# logoi.net
KiCad netlist of a schematic drawn in EAGLE
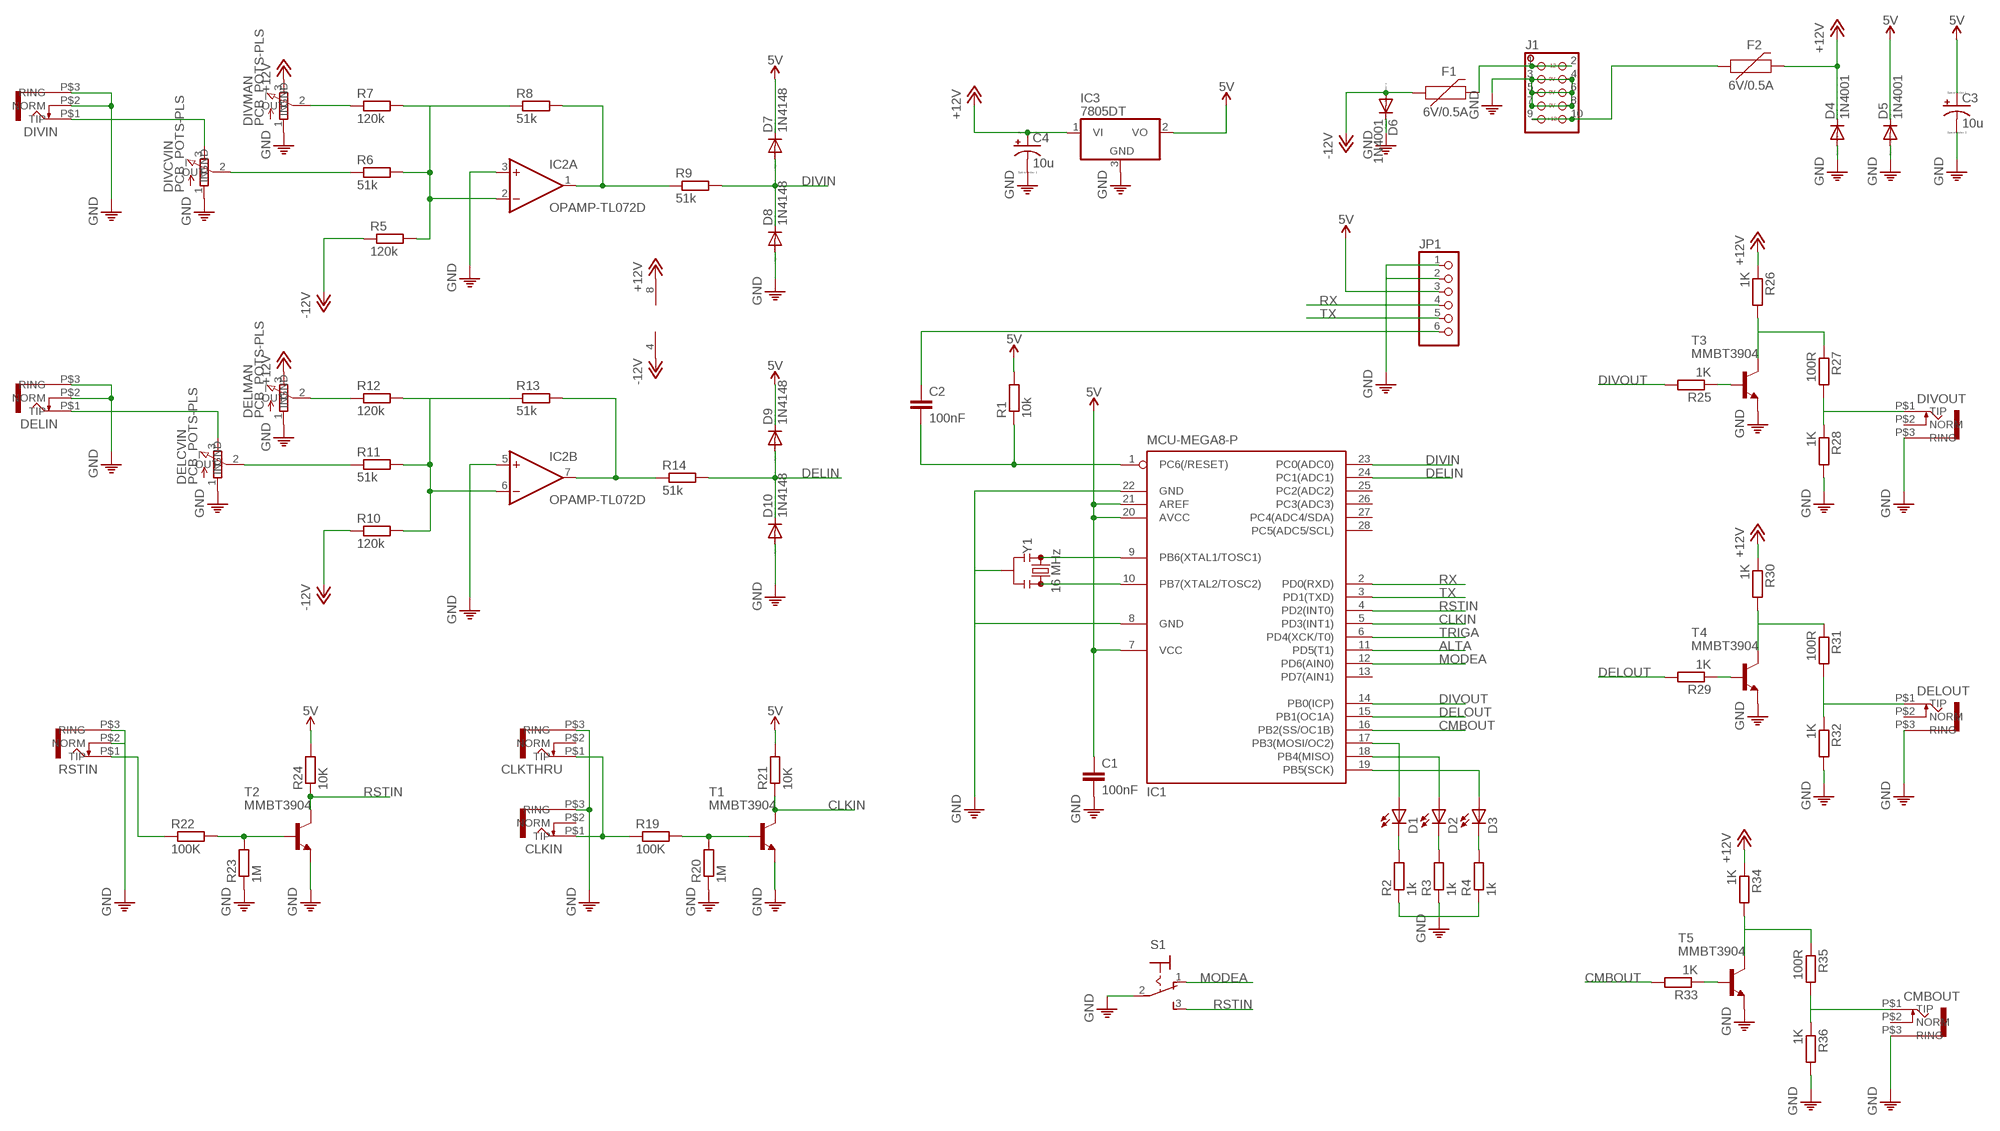
[diagram p0: schematic, sheet 1]

(export (version "E")
  (design (tool "Eeschema 10.0.6"))
  (components
    (comp (ref "C1")
      (value "100nF")
      (footprint "eagle-import:C0603")
      (libsource (lib "eagle-import") (part "CAPACITOR-EUC0603"))
    )
    (comp (ref "C2")
      (value "100nF")
      (footprint "eagle-import:C0603")
      (libsource (lib "eagle-import") (part "CAPACITOR-EUC0603"))
    )
    (comp (ref "C3")
      (value "10u")
      (footprint "eagle-import:E2,5-5")
      (libsource (lib "eagle-import") (part "CAPACITOR_POLARIZED-USE2.5-5"))
    )
    (comp (ref "C4")
      (value "10u")
      (footprint "eagle-import:E2,5-5")
      (libsource (lib "eagle-import") (part "CAPACITOR_POLARIZED-USE2.5-5"))
    )
    (comp (ref "CLKIN")
      (value "VERTICALJACKS")
      (footprint "eagle-import:KOBICONN_PJM301DM_JACK")
      (libsource (lib "eagle-import") (part "VERTICALJACKS"))
    )
    (comp (ref "CLKTHRU")
      (value "VERTICALJACKS")
      (footprint "eagle-import:KOBICONN_PJM301DM_JACK")
      (libsource (lib "eagle-import") (part "VERTICALJACKS"))
    )
    (comp (ref "CMBOUT")
      (value "VERTICALJACKS")
      (footprint "eagle-import:KOBICONN_PJM301DM_JACK")
      (libsource (lib "eagle-import") (part "VERTICALJACKS"))
    )
    (comp (ref "D1")
      (value "LED3MM")
      (footprint "eagle-import:LED3MM")
      (libsource (lib "eagle-import") (part "LED3MM"))
    )
    (comp (ref "D2")
      (value "LED3MM")
      (footprint "eagle-import:LED3MM")
      (libsource (lib "eagle-import") (part "LED3MM"))
    )
    (comp (ref "D3")
      (value "LED3MM")
      (footprint "eagle-import:LED3MM")
      (libsource (lib "eagle-import") (part "LED3MM"))
    )
    (comp (ref "D4")
      (value "1N4001")
      (footprint "eagle-import:DO-214AC")
      (libsource (lib "eagle-import") (part "DIODE-DO-214AC"))
    )
    (comp (ref "D5")
      (value "1N4001")
      (footprint "eagle-import:DO-214AC")
      (libsource (lib "eagle-import") (part "DIODE-DO-214AC"))
    )
    (comp (ref "D6")
      (value "1N4001")
      (footprint "eagle-import:DO-214AC")
      (libsource (lib "eagle-import") (part "DIODE-DO-214AC"))
    )
    (comp (ref "D7")
      (value "1N4148")
      (footprint "eagle-import:SOD323W_INFINEON")
      (libsource (lib "eagle-import") (part "DIODE-1N4148SOD-323"))
    )
    (comp (ref "D8")
      (value "1N4148")
      (footprint "eagle-import:SOD323W_INFINEON")
      (libsource (lib "eagle-import") (part "DIODE-1N4148SOD-323"))
    )
    (comp (ref "D9")
      (value "1N4148")
      (footprint "eagle-import:SOD323W_INFINEON")
      (libsource (lib "eagle-import") (part "DIODE-1N4148SOD-323"))
    )
    (comp (ref "D10")
      (value "1N4148")
      (footprint "eagle-import:SOD323W_INFINEON")
      (libsource (lib "eagle-import") (part "DIODE-1N4148SOD-323"))
    )
    (comp (ref "DELCVIN")
      (value "PCB_POTS-PLS")
      (footprint "eagle-import:9MM_PLS")
      (libsource (lib "eagle-import") (part "PCB_POTS-PLS"))
    )
    (comp (ref "DELIN")
      (value "VERTICALJACKS")
      (footprint "eagle-import:KOBICONN_PJM301DM_JACK")
      (libsource (lib "eagle-import") (part "VERTICALJACKS"))
    )
    (comp (ref "DELMAN")
      (value "PCB_POTS-PLS")
      (footprint "eagle-import:9MM_PLS")
      (libsource (lib "eagle-import") (part "PCB_POTS-PLS"))
    )
    (comp (ref "DELOUT")
      (value "VERTICALJACKS")
      (footprint "eagle-import:KOBICONN_PJM301DM_JACK")
      (libsource (lib "eagle-import") (part "VERTICALJACKS"))
    )
    (comp (ref "DIVCVIN")
      (value "PCB_POTS-PLS")
      (footprint "eagle-import:9MM_PLS")
      (libsource (lib "eagle-import") (part "PCB_POTS-PLS"))
    )
    (comp (ref "DIVIN")
      (value "VERTICALJACKS")
      (footprint "eagle-import:KOBICONN_PJM301DM_JACK")
      (libsource (lib "eagle-import") (part "VERTICALJACKS"))
    )
    (comp (ref "DIVMAN")
      (value "PCB_POTS-PLS")
      (footprint "eagle-import:9MM_PLS")
      (libsource (lib "eagle-import") (part "PCB_POTS-PLS"))
    )
    (comp (ref "DIVOUT")
      (value "VERTICALJACKS")
      (footprint "eagle-import:KOBICONN_PJM301DM_JACK")
      (libsource (lib "eagle-import") (part "VERTICALJACKS"))
    )
    (comp (ref "F1")
      (value "6V/0.5A")
      (footprint "eagle-import:1206")
      (libsource (lib "eagle-import") (part "FUSE-PPTC_HALF-AMP"))
    )
    (comp (ref "F2")
      (value "6V/0.5A")
      (footprint "eagle-import:1206")
      (libsource (lib "eagle-import") (part "FUSE-PPTC_HALF-AMP"))
    )
    (comp (ref "IC1")
      (value "MCU-MEGA8-P")
      (footprint "eagle-import:DIL28-3")
      (libsource (lib "eagle-import") (part "MCU-MEGA8-P"))
    )
    (comp (ref "IC2")
      (value "OPAMP-TL072D")
      (footprint "eagle-import:SO08")
      (libsource (lib "eagle-import") (part "OPAMP-TL072D"))
    )
    (comp (ref "IC3")
      (value "7805DT")
      (footprint "eagle-import:TO252")
      (libsource (lib "eagle-import") (part "78DT05"))
    )
    (comp (ref "J1")
      (value "HEADER-EUROPWR_2X05-OPEN")
      (footprint "eagle-import:2X05_EUROPWR_OPEN")
      (libsource (lib "eagle-import") (part "HEADER-EUROPWR_2X05-OPEN"))
    )
    (comp (ref "JP1")
      (value "PINHD-1X6")
      (footprint "eagle-import:1X06")
      (libsource (lib "eagle-import") (part "PINHD-1X6"))
    )
    (comp (ref "R1")
      (value "10k")
      (footprint "eagle-import:R0603")
      (libsource (lib "eagle-import") (part "RESISTOR-EU_R0603"))
    )
    (comp (ref "R2")
      (value "1k")
      (footprint "eagle-import:R0603")
      (libsource (lib "eagle-import") (part "RESISTOR-EU_R0603"))
    )
    (comp (ref "R3")
      (value "1k")
      (footprint "eagle-import:R0603")
      (libsource (lib "eagle-import") (part "RESISTOR-EU_R0603"))
    )
    (comp (ref "R4")
      (value "1k")
      (footprint "eagle-import:R0603")
      (libsource (lib "eagle-import") (part "RESISTOR-EU_R0603"))
    )
    (comp (ref "R5")
      (value "120k")
      (footprint "eagle-import:R0603")
      (libsource (lib "eagle-import") (part "RESISTOR-EU_R0603"))
    )
    (comp (ref "R6")
      (value "51k")
      (footprint "eagle-import:R0603")
      (libsource (lib "eagle-import") (part "RESISTOR-EU_R0603"))
    )
    (comp (ref "R7")
      (value "120k")
      (footprint "eagle-import:R0603")
      (libsource (lib "eagle-import") (part "RESISTOR-EU_R0603"))
    )
    (comp (ref "R8")
      (value "51k")
      (footprint "eagle-import:R0603")
      (libsource (lib "eagle-import") (part "RESISTOR-EU_R0603"))
    )
    (comp (ref "R9")
      (value "51k")
      (footprint "eagle-import:R0603")
      (libsource (lib "eagle-import") (part "RESISTOR-EU_R0603"))
    )
    (comp (ref "R10")
      (value "120k")
      (footprint "eagle-import:R0603")
      (libsource (lib "eagle-import") (part "RESISTOR-EU_R0603"))
    )
    (comp (ref "R11")
      (value "51k")
      (footprint "eagle-import:R0603")
      (libsource (lib "eagle-import") (part "RESISTOR-EU_R0603"))
    )
    (comp (ref "R12")
      (value "120k")
      (footprint "eagle-import:R0603")
      (libsource (lib "eagle-import") (part "RESISTOR-EU_R0603"))
    )
    (comp (ref "R13")
      (value "51k")
      (footprint "eagle-import:R0603")
      (libsource (lib "eagle-import") (part "RESISTOR-EU_R0603"))
    )
    (comp (ref "R14")
      (value "51k")
      (footprint "eagle-import:R0603")
      (libsource (lib "eagle-import") (part "RESISTOR-EU_R0603"))
    )
    (comp (ref "R19")
      (value "100K")
      (footprint "eagle-import:R0603")
      (libsource (lib "eagle-import") (part "RESISTOR-EU_R0603"))
    )
    (comp (ref "R20")
      (value "1M")
      (footprint "eagle-import:R0603")
      (libsource (lib "eagle-import") (part "RESISTOR-EU_R0603"))
    )
    (comp (ref "R21")
      (value "10K")
      (footprint "eagle-import:R0603")
      (libsource (lib "eagle-import") (part "RESISTOR-EU_R0603"))
    )
    (comp (ref "R22")
      (value "100K")
      (footprint "eagle-import:R0603")
      (libsource (lib "eagle-import") (part "RESISTOR-EU_R0603"))
    )
    (comp (ref "R23")
      (value "1M")
      (footprint "eagle-import:R0603")
      (libsource (lib "eagle-import") (part "RESISTOR-EU_R0603"))
    )
    (comp (ref "R24")
      (value "10K")
      (footprint "eagle-import:R0603")
      (libsource (lib "eagle-import") (part "RESISTOR-EU_R0603"))
    )
    (comp (ref "R25")
      (value "1K")
      (footprint "eagle-import:R0603")
      (libsource (lib "eagle-import") (part "RESISTOR-EU_R0603"))
    )
    (comp (ref "R26")
      (value "1K")
      (footprint "eagle-import:R0603")
      (libsource (lib "eagle-import") (part "RESISTOR-EU_R0603"))
    )
    (comp (ref "R27")
      (value "100R")
      (footprint "eagle-import:R0603")
      (libsource (lib "eagle-import") (part "RESISTOR-EU_R0603"))
    )
    (comp (ref "R28")
      (value "1K")
      (footprint "eagle-import:R0603")
      (libsource (lib "eagle-import") (part "RESISTOR-EU_R0603"))
    )
    (comp (ref "R29")
      (value "1K")
      (footprint "eagle-import:R0603")
      (libsource (lib "eagle-import") (part "RESISTOR-EU_R0603"))
    )
    (comp (ref "R30")
      (value "1K")
      (footprint "eagle-import:R0603")
      (libsource (lib "eagle-import") (part "RESISTOR-EU_R0603"))
    )
    (comp (ref "R31")
      (value "100R")
      (footprint "eagle-import:R0603")
      (libsource (lib "eagle-import") (part "RESISTOR-EU_R0603"))
    )
    (comp (ref "R32")
      (value "1K")
      (footprint "eagle-import:R0603")
      (libsource (lib "eagle-import") (part "RESISTOR-EU_R0603"))
    )
    (comp (ref "R33")
      (value "1K")
      (footprint "eagle-import:R0603")
      (libsource (lib "eagle-import") (part "RESISTOR-EU_R0603"))
    )
    (comp (ref "R34")
      (value "1K")
      (footprint "eagle-import:R0603")
      (libsource (lib "eagle-import") (part "RESISTOR-EU_R0603"))
    )
    (comp (ref "R35")
      (value "100R")
      (footprint "eagle-import:R0603")
      (libsource (lib "eagle-import") (part "RESISTOR-EU_R0603"))
    )
    (comp (ref "R36")
      (value "1K")
      (footprint "eagle-import:R0603")
      (libsource (lib "eagle-import") (part "RESISTOR-EU_R0603"))
    )
    (comp (ref "RSTIN")
      (value "VERTICALJACKS")
      (footprint "eagle-import:KOBICONN_PJM301DM_JACK")
      (libsource (lib "eagle-import") (part "VERTICALJACKS"))
    )
    (comp (ref "S1")
      (value "SWITCH-SPDT-320-916")
      (footprint "eagle-import:320-916")
      (libsource (lib "eagle-import") (part "SWITCH-SPDT-320-916"))
    )
    (comp (ref "T1")
      (value "MMBT3904")
      (footprint "eagle-import:SOT23-BEC")
      (libsource (lib "eagle-import") (part "TRANSISTOR-NPN-SOT23-BECMMBT3904LT1"))
    )
    (comp (ref "T2")
      (value "MMBT3904")
      (footprint "eagle-import:SOT23-BEC")
      (libsource (lib "eagle-import") (part "TRANSISTOR-NPN-SOT23-BECMMBT3904LT1"))
    )
    (comp (ref "T3")
      (value "MMBT3904")
      (footprint "eagle-import:SOT23-BEC")
      (libsource (lib "eagle-import") (part "TRANSISTOR-NPN-SOT23-BECMMBT3904LT1"))
    )
    (comp (ref "T4")
      (value "MMBT3904")
      (footprint "eagle-import:SOT23-BEC")
      (libsource (lib "eagle-import") (part "TRANSISTOR-NPN-SOT23-BECMMBT3904LT1"))
    )
    (comp (ref "T5")
      (value "MMBT3904")
      (footprint "eagle-import:SOT23-BEC")
      (libsource (lib "eagle-import") (part "TRANSISTOR-NPN-SOT23-BECMMBT3904LT1"))
    )
    (comp (ref "Y1")
      (value "16 MHz")
      (footprint "eagle-import:RESONATOR-PTH-7.6X3.8")
      (libsource (lib "eagle-import") (part "RESONATORPTH-7.6X3.8"))
    )
  )
  (nets
    (net (code "1") (name "+12V") (class "Default")
      (node (ref "C4") (pin "+") (pinfunction "+_+") (pintype "passive"))
      (node (ref "D4") (pin "C") (pinfunction "C_C") (pintype "passive"))
      (node (ref "DELMAN") (pin "3") (pinfunction "IN_3") (pintype "passive"))
      (node (ref "DIVMAN") (pin "3") (pinfunction "IN_3") (pintype "passive"))
      (node (ref "F2") (pin "2") (pinfunction "2_2") (pintype "bidirectional"))
      (node (ref "IC2") (pin "8") (pinfunction "V+_8") (pintype "power_in"))
      (node (ref "IC3") (pin "1") (pinfunction "VI_1") (pintype "input"))
      (node (ref "R26") (pin "1") (pinfunction "1_1") (pintype "passive"))
      (node (ref "R30") (pin "1") (pinfunction "1_1") (pintype "passive"))
      (node (ref "R34") (pin "1") (pinfunction "1_1") (pintype "passive"))
    )
    (net (code "2") (name "-12V") (class "Default")
      (node (ref "D6") (pin "A") (pinfunction "A_A") (pintype "passive"))
      (node (ref "F1") (pin "1") (pinfunction "1_1") (pintype "bidirectional"))
      (node (ref "IC2") (pin "4") (pinfunction "V-_4") (pintype "power_in"))
      (node (ref "R10") (pin "1") (pinfunction "1_1") (pintype "passive"))
      (node (ref "R5") (pin "1") (pinfunction "1_1") (pintype "passive"))
    )
    (net (code "3") (name "/ALTA") (class "Default")
      (node (ref "IC1") (pin "11") (pinfunction "PD5(T1)_11") (pintype "bidirectional"))
    )
    (net (code "4") (name "/CLKIN") (class "Default")
      (node (ref "IC1") (pin "5") (pinfunction "PD3(INT1)_5") (pintype "bidirectional"))
      (node (ref "R21") (pin "1") (pinfunction "1_1") (pintype "passive"))
      (node (ref "T1") (pin "C") (pinfunction "C_C") (pintype "passive"))
    )
    (net (code "5") (name "/CMBOUT") (class "Default")
      (node (ref "IC1") (pin "16") (pinfunction "PB2(SS/OC1B)_16") (pintype "bidirectional"))
      (node (ref "R33") (pin "2") (pinfunction "2_2") (pintype "passive"))
    )
    (net (code "6") (name "/DELIN") (class "Default")
      (node (ref "D10") (pin "C") (pinfunction "C_C") (pintype "passive"))
      (node (ref "D9") (pin "A") (pinfunction "A_A") (pintype "passive"))
      (node (ref "IC1") (pin "24") (pinfunction "PC1(ADC1)_24") (pintype "bidirectional"))
      (node (ref "R14") (pin "2") (pinfunction "2_2") (pintype "passive"))
    )
    (net (code "7") (name "/DELOUT") (class "Default")
      (node (ref "IC1") (pin "15") (pinfunction "PB1(OC1A)_15") (pintype "bidirectional"))
      (node (ref "R29") (pin "2") (pinfunction "2_2") (pintype "passive"))
    )
    (net (code "8") (name "/DIVIN") (class "Default")
      (node (ref "D7") (pin "A") (pinfunction "A_A") (pintype "passive"))
      (node (ref "D8") (pin "C") (pinfunction "C_C") (pintype "passive"))
      (node (ref "IC1") (pin "23") (pinfunction "PC0(ADC0)_23") (pintype "bidirectional"))
      (node (ref "R9") (pin "2") (pinfunction "2_2") (pintype "passive"))
    )
    (net (code "9") (name "/DIVOUT") (class "Default")
      (node (ref "IC1") (pin "14") (pinfunction "PB0(ICP)_14") (pintype "bidirectional"))
      (node (ref "R25") (pin "2") (pinfunction "2_2") (pintype "passive"))
    )
    (net (code "10") (name "/MODEA") (class "Default")
      (node (ref "IC1") (pin "12") (pinfunction "PD6(AIN0)_12") (pintype "bidirectional"))
      (node (ref "S1") (pin "1") (pinfunction "O_1") (pintype "passive"))
    )
    (net (code "11") (name "/RSTIN") (class "Default")
      (node (ref "IC1") (pin "4") (pinfunction "PD2(INT0)_4") (pintype "bidirectional"))
      (node (ref "R24") (pin "1") (pinfunction "1_1") (pintype "passive"))
      (node (ref "S1") (pin "3") (pinfunction "S_3") (pintype "passive"))
      (node (ref "T2") (pin "C") (pinfunction "C_C") (pintype "passive"))
    )
    (net (code "12") (name "/RX") (class "Default")
      (node (ref "IC1") (pin "2") (pinfunction "PD0(RXD)_2") (pintype "bidirectional"))
      (node (ref "JP1") (pin "4") (pinfunction "4_4") (pintype "passive"))
    )
    (net (code "13") (name "/TRIGA") (class "Default")
      (node (ref "IC1") (pin "6") (pinfunction "PD4(XCK/T0)_6") (pintype "bidirectional"))
    )
    (net (code "14") (name "/TX") (class "Default")
      (node (ref "IC1") (pin "3") (pinfunction "PD1(TXD)_3") (pintype "bidirectional"))
      (node (ref "JP1") (pin "5") (pinfunction "5_5") (pintype "passive"))
    )
    (net (code "15") (name "5V") (class "Default")
      (node (ref "C1") (pin "1") (pinfunction "1_1") (pintype "passive"))
      (node (ref "C3") (pin "+") (pinfunction "+_+") (pintype "passive"))
      (node (ref "D5") (pin "C") (pinfunction "C_C") (pintype "passive"))
      (node (ref "D7") (pin "C") (pinfunction "C_C") (pintype "passive"))
      (node (ref "D9") (pin "C") (pinfunction "C_C") (pintype "passive"))
      (node (ref "IC1") (pin "20") (pinfunction "AVCC_20") (pintype "power_in"))
      (node (ref "IC1") (pin "21") (pinfunction "AREF_21") (pintype "passive"))
      (node (ref "IC1") (pin "7") (pinfunction "VCC_7") (pintype "power_in"))
      (node (ref "IC3") (pin "2") (pinfunction "VO_2") (pintype "passive"))
      (node (ref "JP1") (pin "3") (pinfunction "3_3") (pintype "passive"))
      (node (ref "R1") (pin "2") (pinfunction "2_2") (pintype "passive"))
      (node (ref "R21") (pin "2") (pinfunction "2_2") (pintype "passive"))
      (node (ref "R24") (pin "2") (pinfunction "2_2") (pintype "passive"))
    )
    (net (code "16") (name "GND") (class "Default")
      (node (ref "C1") (pin "2") (pinfunction "2_2") (pintype "passive"))
      (node (ref "C3") (pin "-") (pinfunction "-_-") (pintype "passive"))
      (node (ref "C4") (pin "-") (pinfunction "-_-") (pintype "passive"))
      (node (ref "CLKIN") (pin "P$3") (pinfunction "RING_P$3") (pintype "passive"))
      (node (ref "CLKTHRU") (pin "P$3") (pinfunction "RING_P$3") (pintype "passive"))
      (node (ref "CMBOUT") (pin "P$3") (pinfunction "RING_P$3") (pintype "passive"))
      (node (ref "D10") (pin "A") (pinfunction "A_A") (pintype "passive"))
      (node (ref "D4") (pin "A") (pinfunction "A_A") (pintype "passive"))
      (node (ref "D5") (pin "A") (pinfunction "A_A") (pintype "passive"))
      (node (ref "D6") (pin "C") (pinfunction "C_C") (pintype "passive"))
      (node (ref "D8") (pin "A") (pinfunction "A_A") (pintype "passive"))
      (node (ref "DELCVIN") (pin "1") (pinfunction "GND_1") (pintype "passive"))
      (node (ref "DELIN") (pin "P$2") (pinfunction "NORM_P$2") (pintype "passive"))
      (node (ref "DELIN") (pin "P$3") (pinfunction "RING_P$3") (pintype "passive"))
      (node (ref "DELMAN") (pin "1") (pinfunction "GND_1") (pintype "passive"))
      (node (ref "DELOUT") (pin "P$3") (pinfunction "RING_P$3") (pintype "passive"))
      (node (ref "DIVCVIN") (pin "1") (pinfunction "GND_1") (pintype "passive"))
      (node (ref "DIVIN") (pin "P$2") (pinfunction "NORM_P$2") (pintype "passive"))
      (node (ref "DIVIN") (pin "P$3") (pinfunction "RING_P$3") (pintype "passive"))
      (node (ref "DIVMAN") (pin "1") (pinfunction "GND_1") (pintype "passive"))
      (node (ref "DIVOUT") (pin "P$3") (pinfunction "RING_P$3") (pintype "passive"))
      (node (ref "IC1") (pin "22") (pinfunction "GND_22") (pintype "power_in"))
      (node (ref "IC1") (pin "8") (pinfunction "GND_8") (pintype "power_in"))
      (node (ref "IC2") (pin "3") (pinfunction "+IN_3") (pintype "input"))
      (node (ref "IC2") (pin "5") (pinfunction "+IN_5") (pintype "input"))
      (node (ref "IC3") (pin "3") (pinfunction "GND_3") (pintype "passive"))
      (node (ref "J1") (pin "3") (pinfunction "3_3") (pintype "passive"))
      (node (ref "J1") (pin "4") (pinfunction "4_4") (pintype "passive"))
      (node (ref "J1") (pin "5") (pinfunction "5_5") (pintype "passive"))
      (node (ref "J1") (pin "6") (pinfunction "6_6") (pintype "passive"))
      (node (ref "J1") (pin "7") (pinfunction "7_7") (pintype "passive"))
      (node (ref "J1") (pin "8") (pinfunction "8_8") (pintype "passive"))
      (node (ref "JP1") (pin "1") (pinfunction "1_1") (pintype "passive"))
      (node (ref "JP1") (pin "2") (pinfunction "2_2") (pintype "passive"))
      (node (ref "R2") (pin "1") (pinfunction "1_1") (pintype "passive"))
      (node (ref "R20") (pin "1") (pinfunction "1_1") (pintype "passive"))
      (node (ref "R23") (pin "1") (pinfunction "1_1") (pintype "passive"))
      (node (ref "R28") (pin "2") (pinfunction "2_2") (pintype "passive"))
      (node (ref "R3") (pin "1") (pinfunction "1_1") (pintype "passive"))
      (node (ref "R32") (pin "2") (pinfunction "2_2") (pintype "passive"))
      (node (ref "R36") (pin "2") (pinfunction "2_2") (pintype "passive"))
      (node (ref "R4") (pin "1") (pinfunction "1_1") (pintype "passive"))
      (node (ref "RSTIN") (pin "P$2") (pinfunction "NORM_P$2") (pintype "passive"))
      (node (ref "RSTIN") (pin "P$3") (pinfunction "RING_P$3") (pintype "passive"))
      (node (ref "S1") (pin "2") (pinfunction "P_2") (pintype "passive"))
      (node (ref "T1") (pin "E") (pinfunction "E_E") (pintype "passive"))
      (node (ref "T2") (pin "E") (pinfunction "E_E") (pintype "passive"))
      (node (ref "T3") (pin "E") (pinfunction "E_E") (pintype "passive"))
      (node (ref "T4") (pin "E") (pinfunction "E_E") (pintype "passive"))
      (node (ref "T5") (pin "E") (pinfunction "E_E") (pintype "passive"))
      (node (ref "Y1") (pin "2") (pinfunction "2_2") (pintype "passive"))
    )
    (net (code "17") (name "Net-(C2-Pad1)") (class "Default")
      (node (ref "C2") (pin "1") (pinfunction "1_1") (pintype "passive"))
      (node (ref "JP1") (pin "6") (pinfunction "6_6") (pintype "passive"))
    )
    (net (code "18") (name "Net-(CLKIN-TIP)") (class "Default")
      (node (ref "CLKIN") (pin "P$1") (pinfunction "TIP_P$1") (pintype "passive"))
      (node (ref "CLKTHRU") (pin "P$1") (pinfunction "TIP_P$1") (pintype "passive"))
      (node (ref "R19") (pin "1") (pinfunction "1_1") (pintype "passive"))
    )
    (net (code "19") (name "Net-(CMBOUT-TIP)") (class "Default")
      (node (ref "CMBOUT") (pin "P$1") (pinfunction "TIP_P$1") (pintype "passive"))
      (node (ref "R35") (pin "2") (pinfunction "2_2") (pintype "passive"))
      (node (ref "R36") (pin "1") (pinfunction "1_1") (pintype "passive"))
    )
    (net (code "20") (name "Net-(D1-C)") (class "Default")
      (node (ref "D1") (pin "K") (pinfunction "C_K") (pintype "passive"))
      (node (ref "R2") (pin "2") (pinfunction "2_2") (pintype "passive"))
    )
    (net (code "21") (name "Net-(D2-C)") (class "Default")
      (node (ref "D2") (pin "K") (pinfunction "C_K") (pintype "passive"))
      (node (ref "R3") (pin "2") (pinfunction "2_2") (pintype "passive"))
    )
    (net (code "22") (name "Net-(D3-C)") (class "Default")
      (node (ref "D3") (pin "K") (pinfunction "C_K") (pintype "passive"))
      (node (ref "R4") (pin "2") (pinfunction "2_2") (pintype "passive"))
    )
    (net (code "23") (name "Net-(DELCVIN-IN)") (class "Default")
      (node (ref "DELCVIN") (pin "3") (pinfunction "IN_3") (pintype "passive"))
      (node (ref "DELIN") (pin "P$1") (pinfunction "TIP_P$1") (pintype "passive"))
    )
    (net (code "24") (name "Net-(DELCVIN-OUT)") (class "Default")
      (node (ref "DELCVIN") (pin "2") (pinfunction "OUT_2") (pintype "passive"))
      (node (ref "R11") (pin "1") (pinfunction "1_1") (pintype "passive"))
    )
    (net (code "25") (name "Net-(DELMAN-OUT)") (class "Default")
      (node (ref "DELMAN") (pin "2") (pinfunction "OUT_2") (pintype "passive"))
      (node (ref "R12") (pin "1") (pinfunction "1_1") (pintype "passive"))
    )
    (net (code "26") (name "Net-(DELOUT-TIP)") (class "Default")
      (node (ref "DELOUT") (pin "P$1") (pinfunction "TIP_P$1") (pintype "passive"))
      (node (ref "R31") (pin "2") (pinfunction "2_2") (pintype "passive"))
      (node (ref "R32") (pin "1") (pinfunction "1_1") (pintype "passive"))
    )
    (net (code "27") (name "Net-(DIVCVIN-IN)") (class "Default")
      (node (ref "DIVCVIN") (pin "3") (pinfunction "IN_3") (pintype "passive"))
      (node (ref "DIVIN") (pin "P$1") (pinfunction "TIP_P$1") (pintype "passive"))
    )
    (net (code "28") (name "Net-(DIVCVIN-OUT)") (class "Default")
      (node (ref "DIVCVIN") (pin "2") (pinfunction "OUT_2") (pintype "passive"))
      (node (ref "R6") (pin "1") (pinfunction "1_1") (pintype "passive"))
    )
    (net (code "29") (name "Net-(DIVMAN-OUT)") (class "Default")
      (node (ref "DIVMAN") (pin "2") (pinfunction "OUT_2") (pintype "passive"))
      (node (ref "R7") (pin "1") (pinfunction "1_1") (pintype "passive"))
    )
    (net (code "30") (name "Net-(DIVOUT-TIP)") (class "Default")
      (node (ref "DIVOUT") (pin "P$1") (pinfunction "TIP_P$1") (pintype "passive"))
      (node (ref "R27") (pin "2") (pinfunction "2_2") (pintype "passive"))
      (node (ref "R28") (pin "1") (pinfunction "1_1") (pintype "passive"))
    )
    (net (code "31") (name "Net-(F1-Pad2)") (class "Default")
      (node (ref "F1") (pin "2") (pinfunction "2_2") (pintype "bidirectional"))
      (node (ref "J1") (pin "1") (pinfunction "1_1") (pintype "passive"))
      (node (ref "J1") (pin "2") (pinfunction "2_2") (pintype "passive"))
    )
    (net (code "32") (name "Net-(F2-Pad1)") (class "Default")
      (node (ref "F2") (pin "1") (pinfunction "1_1") (pintype "bidirectional"))
      (node (ref "J1") (pin "10") (pinfunction "10_10") (pintype "passive"))
      (node (ref "J1") (pin "9") (pinfunction "9_9") (pintype "passive"))
    )
    (net (code "33") (name "Net-(IC1-PB3(MOSI{slash}OC2))") (class "Default")
      (node (ref "D1") (pin "A") (pinfunction "A_A") (pintype "passive"))
      (node (ref "IC1") (pin "17") (pinfunction "PB3(MOSI/OC2)_17") (pintype "bidirectional"))
    )
    (net (code "34") (name "Net-(IC1-PB4(MISO))") (class "Default")
      (node (ref "D2") (pin "A") (pinfunction "A_A") (pintype "passive"))
      (node (ref "IC1") (pin "18") (pinfunction "PB4(MISO)_18") (pintype "bidirectional"))
    )
    (net (code "35") (name "Net-(IC1-PB5(SCK))") (class "Default")
      (node (ref "D3") (pin "A") (pinfunction "A_A") (pintype "passive"))
      (node (ref "IC1") (pin "19") (pinfunction "PB5(SCK)_19") (pintype "bidirectional"))
    )
    (net (code "36") (name "Net-(IC1-PB6(XTAL1{slash}TOSC1))") (class "Default")
      (node (ref "IC1") (pin "9") (pinfunction "PB6(XTAL1/TOSC1)_9") (pintype "bidirectional"))
      (node (ref "Y1") (pin "1") (pinfunction "1_1") (pintype "passive"))
    )
    (net (code "37") (name "Net-(IC1-PB7(XTAL2{slash}TOSC2))") (class "Default")
      (node (ref "IC1") (pin "10") (pinfunction "PB7(XTAL2/TOSC2)_10") (pintype "bidirectional"))
      (node (ref "Y1") (pin "3") (pinfunction "3_3") (pintype "passive"))
    )
    (net (code "38") (name "Net-(IC1-PC6({slash}RESET))") (class "Default")
      (node (ref "C2") (pin "2") (pinfunction "2_2") (pintype "passive"))
      (node (ref "IC1") (pin "1") (pinfunction "PC6(/RESET)_1") (pintype "bidirectional"))
      (node (ref "R1") (pin "1") (pinfunction "1_1") (pintype "passive"))
    )
    (net (code "39") (name "Net-(IC2A--IN)") (class "Default")
      (node (ref "IC2") (pin "2") (pinfunction "-IN_2") (pintype "input"))
      (node (ref "R5") (pin "2") (pinfunction "2_2") (pintype "passive"))
      (node (ref "R6") (pin "2") (pinfunction "2_2") (pintype "passive"))
      (node (ref "R7") (pin "2") (pinfunction "2_2") (pintype "passive"))
      (node (ref "R8") (pin "1") (pinfunction "1_1") (pintype "passive"))
    )
    (net (code "40") (name "Net-(IC2A-OUT)") (class "Default")
      (node (ref "IC2") (pin "1") (pinfunction "OUT_1") (pintype "output"))
      (node (ref "R8") (pin "2") (pinfunction "2_2") (pintype "passive"))
      (node (ref "R9") (pin "1") (pinfunction "1_1") (pintype "passive"))
    )
    (net (code "41") (name "Net-(IC2B--IN)") (class "Default")
      (node (ref "IC2") (pin "6") (pinfunction "-IN_6") (pintype "input"))
      (node (ref "R10") (pin "2") (pinfunction "2_2") (pintype "passive"))
      (node (ref "R11") (pin "2") (pinfunction "2_2") (pintype "passive"))
      (node (ref "R12") (pin "2") (pinfunction "2_2") (pintype "passive"))
      (node (ref "R13") (pin "1") (pinfunction "1_1") (pintype "passive"))
    )
    (net (code "42") (name "Net-(IC2B-OUT)") (class "Default")
      (node (ref "IC2") (pin "7") (pinfunction "OUT_7") (pintype "output"))
      (node (ref "R13") (pin "2") (pinfunction "2_2") (pintype "passive"))
      (node (ref "R14") (pin "1") (pinfunction "1_1") (pintype "passive"))
    )
    (net (code "43") (name "Net-(R19-Pad2)") (class "Default")
      (node (ref "R19") (pin "2") (pinfunction "2_2") (pintype "passive"))
      (node (ref "R20") (pin "2") (pinfunction "2_2") (pintype "passive"))
      (node (ref "T1") (pin "B") (pinfunction "B_B") (pintype "passive"))
    )
    (net (code "44") (name "Net-(R22-Pad2)") (class "Default")
      (node (ref "R22") (pin "2") (pinfunction "2_2") (pintype "passive"))
      (node (ref "R23") (pin "2") (pinfunction "2_2") (pintype "passive"))
      (node (ref "T2") (pin "B") (pinfunction "B_B") (pintype "passive"))
    )
    (net (code "45") (name "Net-(R25-Pad1)") (class "Default")
      (node (ref "R25") (pin "1") (pinfunction "1_1") (pintype "passive"))
      (node (ref "T3") (pin "B") (pinfunction "B_B") (pintype "passive"))
    )
    (net (code "46") (name "Net-(R26-Pad2)") (class "Default")
      (node (ref "R26") (pin "2") (pinfunction "2_2") (pintype "passive"))
      (node (ref "R27") (pin "1") (pinfunction "1_1") (pintype "passive"))
      (node (ref "T3") (pin "C") (pinfunction "C_C") (pintype "passive"))
    )
    (net (code "47") (name "Net-(R29-Pad1)") (class "Default")
      (node (ref "R29") (pin "1") (pinfunction "1_1") (pintype "passive"))
      (node (ref "T4") (pin "B") (pinfunction "B_B") (pintype "passive"))
    )
    (net (code "48") (name "Net-(R30-Pad2)") (class "Default")
      (node (ref "R30") (pin "2") (pinfunction "2_2") (pintype "passive"))
      (node (ref "R31") (pin "1") (pinfunction "1_1") (pintype "passive"))
      (node (ref "T4") (pin "C") (pinfunction "C_C") (pintype "passive"))
    )
    (net (code "49") (name "Net-(R33-Pad1)") (class "Default")
      (node (ref "R33") (pin "1") (pinfunction "1_1") (pintype "passive"))
      (node (ref "T5") (pin "B") (pinfunction "B_B") (pintype "passive"))
    )
    (net (code "50") (name "Net-(R34-Pad2)") (class "Default")
      (node (ref "R34") (pin "2") (pinfunction "2_2") (pintype "passive"))
      (node (ref "R35") (pin "1") (pinfunction "1_1") (pintype "passive"))
      (node (ref "T5") (pin "C") (pinfunction "C_C") (pintype "passive"))
    )
    (net (code "51") (name "Net-(RSTIN-TIP)") (class "Default")
      (node (ref "R22") (pin "1") (pinfunction "1_1") (pintype "passive"))
      (node (ref "RSTIN") (pin "P$1") (pinfunction "TIP_P$1") (pintype "passive"))
    )
    (net (code "52") (name "unconnected-(CLKIN-NORM-PadP$2)") (class "Default")
      (node (ref "CLKIN") (pin "P$2") (pinfunction "NORM_P$2") (pintype "passive"))
    )
    (net (code "53") (name "unconnected-(CLKTHRU-NORM-PadP$2)") (class "Default")
      (node (ref "CLKTHRU") (pin "P$2") (pinfunction "NORM_P$2") (pintype "passive"))
    )
    (net (code "54") (name "unconnected-(CMBOUT-NORM-PadP$2)") (class "Default")
      (node (ref "CMBOUT") (pin "P$2") (pinfunction "NORM_P$2") (pintype "passive"))
    )
    (net (code "55") (name "unconnected-(DELOUT-NORM-PadP$2)") (class "Default")
      (node (ref "DELOUT") (pin "P$2") (pinfunction "NORM_P$2") (pintype "passive"))
    )
    (net (code "56") (name "unconnected-(DIVOUT-NORM-PadP$2)") (class "Default")
      (node (ref "DIVOUT") (pin "P$2") (pinfunction "NORM_P$2") (pintype "passive"))
    )
    (net (code "57") (name "unconnected-(IC1-PC2(ADC2)-Pad25)") (class "Default")
      (node (ref "IC1") (pin "25") (pinfunction "PC2(ADC2)_25") (pintype "bidirectional"))
    )
    (net (code "58") (name "unconnected-(IC1-PC3(ADC3)-Pad26)") (class "Default")
      (node (ref "IC1") (pin "26") (pinfunction "PC3(ADC3)_26") (pintype "bidirectional"))
    )
    (net (code "59") (name "unconnected-(IC1-PC4(ADC4{slash}SDA)-Pad27)") (class "Default")
      (node (ref "IC1") (pin "27") (pinfunction "PC4(ADC4/SDA)_27") (pintype "bidirectional"))
    )
    (net (code "60") (name "unconnected-(IC1-PC5(ADC5{slash}SCL)-Pad28)") (class "Default")
      (node (ref "IC1") (pin "28") (pinfunction "PC5(ADC5/SCL)_28") (pintype "bidirectional"))
    )
    (net (code "61") (name "unconnected-(IC1-PD7(AIN1)-Pad13)") (class "Default")
      (node (ref "IC1") (pin "13") (pinfunction "PD7(AIN1)_13") (pintype "bidirectional"))
    )
  )
)
